# top.net
KiCad netlist of a schematic drawn in Altium Designer
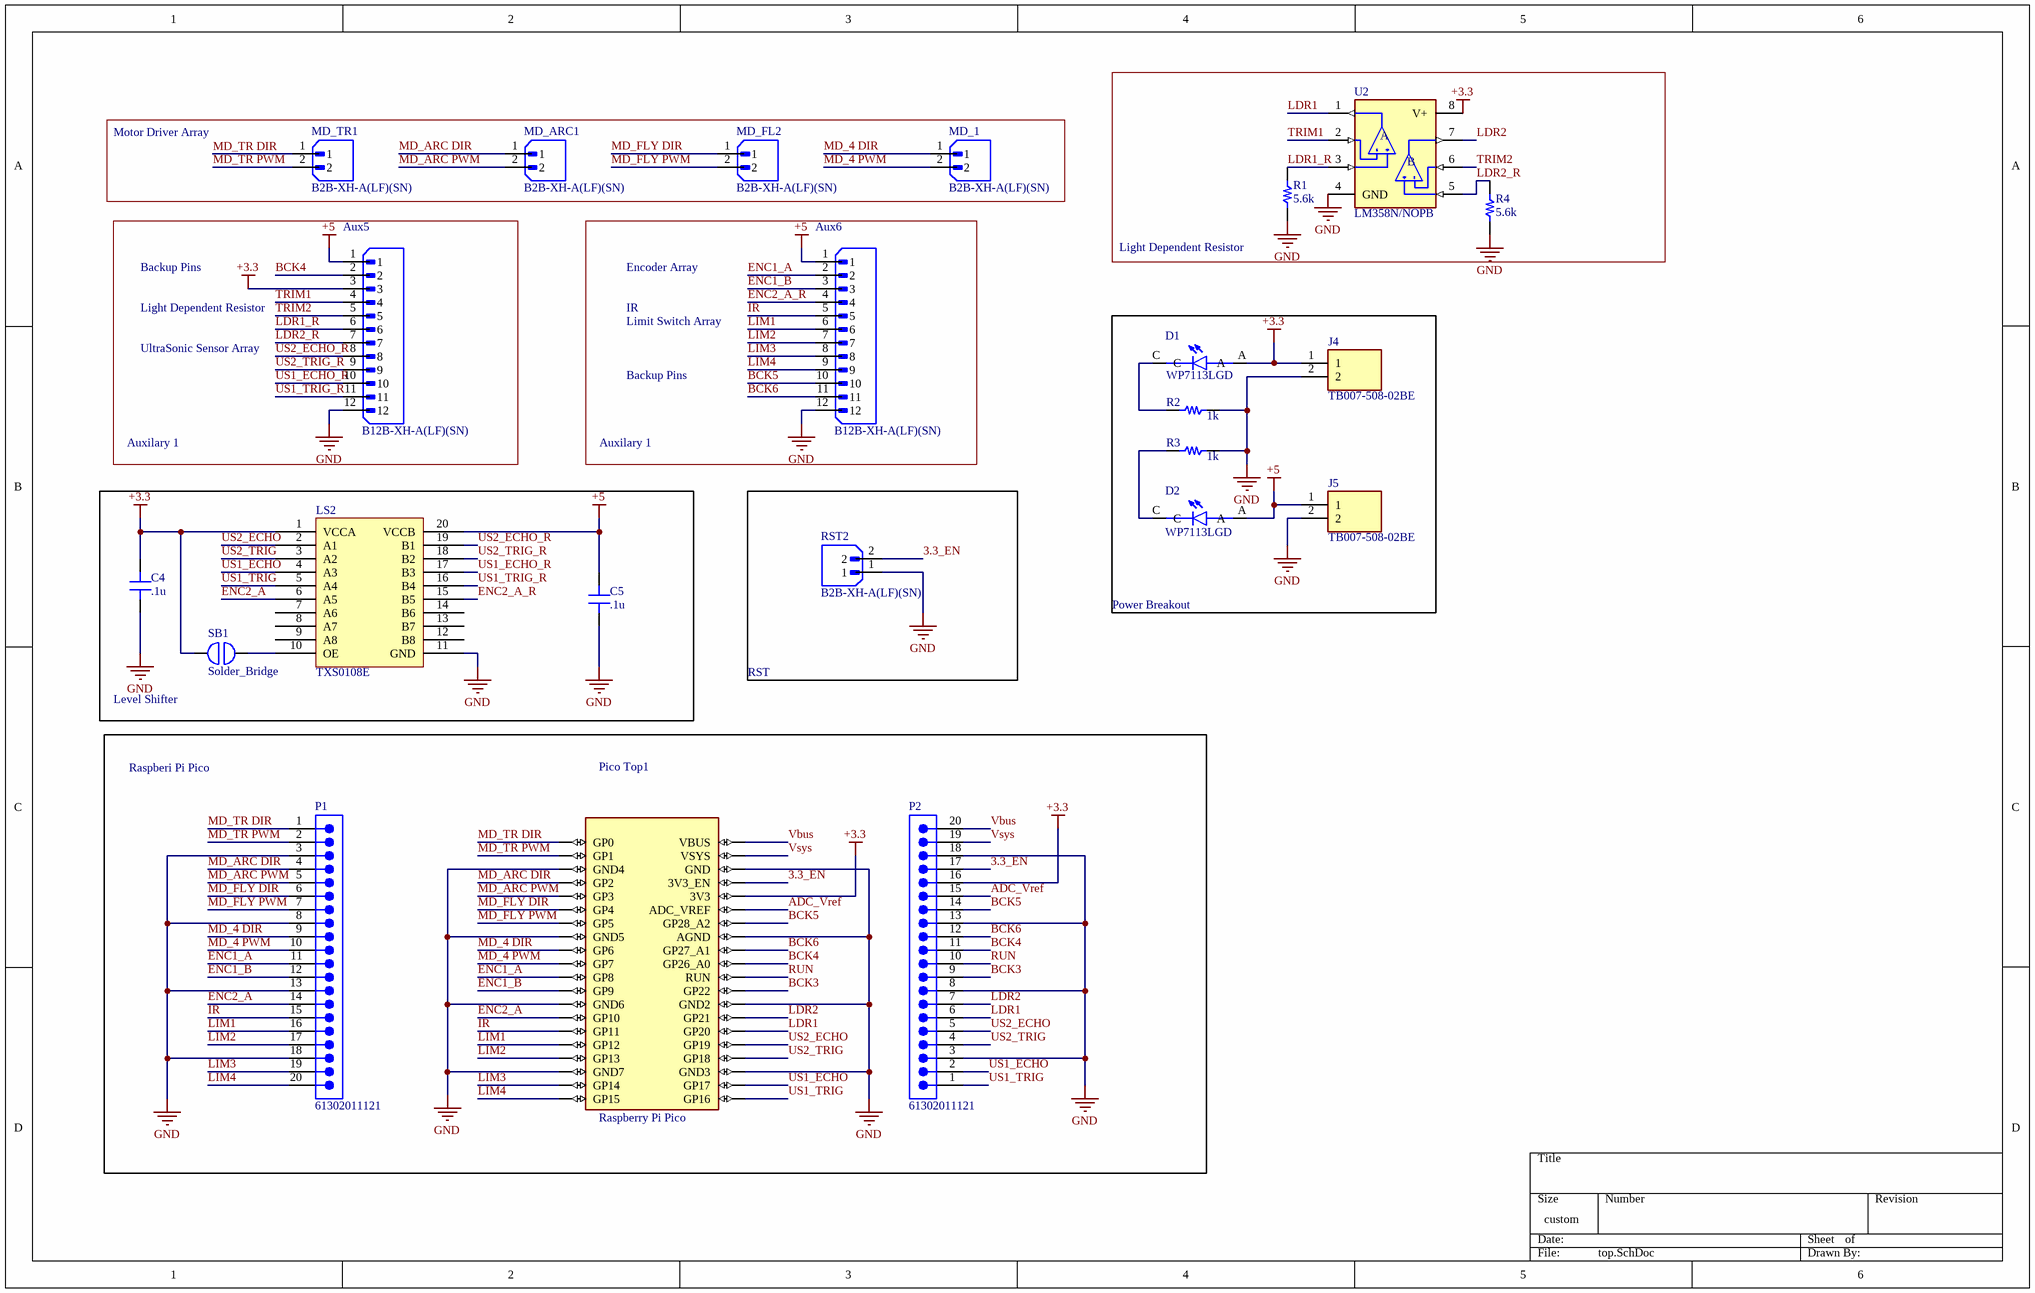
[diagram p0: top.SchDoc]

(export (version "E")
  (design (tool "Eeschema 10.0.6"))
  (components
    (comp (ref "Aux5")
      (value "B12B-XH-A(LF)(SN)")
      (footprint "JST_B12B-XH-A(LF)(SN)")
      (description "Connector Header Through Hole 12 position 0.098 (2.50mm)")
      (fields (field (name "MF") "JST Sales"))
      (libsource (lib "CSD Robocon Workspace") (part "B12B-XH-A(LF)(SN)"))
    )
    (comp (ref "Aux6")
      (value "B12B-XH-A(LF)(SN)")
      (footprint "JST_B12B-XH-A(LF)(SN)")
      (description "Connector Header Through Hole 12 position 0.098 (2.50mm)")
      (fields (field (name "MF") "JST Sales"))
      (libsource (lib "CSD Robocon Workspace") (part "B12B-XH-A(LF)(SN)"))
    )
    (comp (ref "C4")
      (value ".1u")
      (footprint "generic_cap")
      (description "Generic Ceramic Capacitor")
      (fields (field (name "MP") "RDER71H472K0K1H03B"))
      (libsource (lib "CSD Robocon Workspace") (part "generic_cap"))
    )
    (comp (ref "C5")
      (value ".1u")
      (footprint "generic_cap")
      (description "Generic Ceramic Capacitor")
      (fields (field (name "MP") "RDER71H472K0K1H03B"))
      (libsource (lib "CSD Robocon Workspace") (part "generic_cap"))
    )
    (comp (ref "D1")
      (value "WP7113LGD")
      (footprint "LED_WP7113LGD")
      (description "Green 568nm LED Indication - Discrete 1.9V Radial")
      (fields (field (name "MF") "Kingbright"))
      (libsource (lib "CSD Robocon Workspace") (part "WP7113LGD"))
    )
    (comp (ref "D2")
      (value "WP7113LGD")
      (footprint "LED_WP7113LGD")
      (description "Green 568nm LED Indication - Discrete 1.9V Radial")
      (fields (field (name "MF") "Kingbright"))
      (libsource (lib "CSD Robocon Workspace") (part "WP7113LGD"))
    )
    (comp (ref "J4")
      (value "TB007-508-02BE")
      (footprint "CUI_TB007-508-02BE")
      (description "Barrier Strip Terminal Block")
      (fields (field (name "MF") "{'manufacturer': u'CUI'}"))
      (libsource (lib "CSD Robocon Workspace") (part "TB007-508-02BE"))
    )
    (comp (ref "J5")
      (value "TB007-508-02BE")
      (footprint "CUI_TB007-508-02BE")
      (description "Barrier Strip Terminal Block")
      (fields (field (name "MF") "{'manufacturer': u'CUI'}"))
      (libsource (lib "CSD Robocon Workspace") (part "TB007-508-02BE"))
    )
    (comp (ref "LS2")
      (value "TXS0108E")
      (footprint "TXS0108E footprint")
      (description "8 Channel Logic Level Shifter module")
      (libsource (lib "CSD Robocon Workspace") (part "TXS0108E Symbol"))
    )
    (comp (ref "MD_1")
      (value "B2B-XH-A(LF)(SN)")
      (footprint "JST_B2B-XH-A(LF)(SN)")
      (description "Connector Header Through Hole 2 position 0.098 (2.50mm)")
      (fields (field (name "MF") "JST Sales America Inc."))
      (libsource (lib "") (part "B2B-XH-A(LF)(SN)_2"))
    )
    (comp (ref "MD_ARC1")
      (value "B2B-XH-A(LF)(SN)")
      (footprint "JST_B2B-XH-A(LF)(SN)")
      (description "Connector Header Through Hole 2 position 0.098 (2.50mm)")
      (fields (field (name "MF") "JST Sales America Inc."))
      (libsource (lib "") (part "B2B-XH-A(LF)(SN)_2"))
    )
    (comp (ref "MD_FL2")
      (value "B2B-XH-A(LF)(SN)")
      (footprint "JST_B2B-XH-A(LF)(SN)")
      (description "Connector Header Through Hole 2 position 0.098 (2.50mm)")
      (fields (field (name "MF") "JST Sales America Inc."))
      (libsource (lib "") (part "B2B-XH-A(LF)(SN)_2"))
    )
    (comp (ref "MD_TR1")
      (value "B2B-XH-A(LF)(SN)")
      (footprint "JST_B2B-XH-A(LF)(SN)")
      (description "Connector Header Through Hole 2 position 0.098 (2.50mm)")
      (fields (field (name "MF") "JST Sales America Inc."))
      (libsource (lib "CSD Robocon Workspace") (part "B2B-XH-A(LF)(SN)"))
    )
    (comp (ref "P1")
      (value "61302011121")
      (footprint "61302011121")
      (description "WR-PHD Pin Header, THT, Vertical, pitch 2.54mm, 1 Row, 20P")
      (fields (field (name "MANUFACTURER") "Wurth Elektronik"))
      (libsource (lib "CSD Robocon Workspace") (part "62002011121"))
    )
    (comp (ref "P2")
      (value "61302011121")
      (footprint "61302011121")
      (description "WR-PHD Pin Header, THT, Vertical, pitch 2.54mm, 1 Row, 20P")
      (fields (field (name "MANUFACTURER") "Wurth Elektronik"))
      (libsource (lib "CSD Robocon Workspace") (part "62002011121"))
    )
    (comp (ref "Pico Top1")
      (value "Raspberry Pi Pico")
      (footprint "RASPBERRY_PI_PICO")
      (description "Raspberry Pi Board, Arm Cortex-M0+")
      (fields (field (name "MF") "Raspberry Pi") (field (name "MP") "RASPBERRY PI PICO"))
      (libsource (lib "CSD Robocon Workspace") (part "Raspberry Pi Pico"))
    )
    (comp (ref "R1")
      (value "5.6k")
      (footprint "generic_res_footprint")
      (description "Generic through hole resistor")
      (libsource (lib "CSD Robocon Workspace") (part "generic_res"))
    )
    (comp (ref "R2")
      (value "1k")
      (footprint "generic_res_footprint")
      (description "Generic through hole resistor")
      (libsource (lib "CSD Robocon Workspace") (part "generic_res"))
    )
    (comp (ref "R3")
      (value "1k")
      (footprint "generic_res_footprint")
      (description "Generic through hole resistor")
      (libsource (lib "CSD Robocon Workspace") (part "generic_res"))
    )
    (comp (ref "R4")
      (value "5.6k")
      (footprint "generic_res_footprint")
      (description "Generic through hole resistor")
      (libsource (lib "CSD Robocon Workspace") (part "generic_res"))
    )
    (comp (ref "RST2")
      (value "B2B-XH-A(LF)(SN)")
      (footprint "JST_B2B-XH-A(LF)(SN)")
      (description "Connector Header Through Hole 2 position 0.098 (2.50mm)")
      (fields (field (name "MF") "JST Sales America Inc."))
      (libsource (lib "") (part "B2B-XH-A(LF)(SN)_1"))
    )
    (comp (ref "SB1")
      (value "Solder_Bridge")
      (footprint "Solder_Bridge-Footprint-1")
      (description "Solder bridge component")
      (libsource (lib "CSD Robocon Workspace") (part "SB_SYM"))
    )
    (comp (ref "U2")
      (value "LM358N/NOPB")
      (footprint "DIP794W45P254L959H508Q8")
      (description "General Purpose Amplifier 2 Circuit - 8-PDIP")
      (fields (field (name "MP") "LM358N") (field (name "MF") "ON Semiconductor"))
      (libsource (lib "CSD Robocon Workspace") (part "LM358N/NOPB"))
    )
  )
  (nets
    (net (code "1") (name "+3.3") (class "Default")
      (node (ref "Aux5") (pin "3") (pinfunction "3_3") (pintype "passive"))
      (node (ref "C4") (pin "2") (pinfunction "2_2") (pintype "passive"))
      (node (ref "D1") (pin "A") (pinfunction "A_A") (pintype "passive"))
      (node (ref "J4") (pin "1") (pinfunction "1_1") (pintype "passive"))
      (node (ref "LS2") (pin "1") (pinfunction "VCCA_1") (pintype "passive"))
      (node (ref "P2") (pin "16") (pinfunction "16_16") (pintype "passive"))
      (node (ref "Pico Top1") (pin "3V3") (pinfunction "3V3_3V3") (pintype "bidirectional"))
      (node (ref "SB1") (pin "1") (pinfunction "1_1") (pintype "passive"))
      (node (ref "U2") (pin "8") (pinfunction "V+_8") (pintype "power_in"))
    )
    (net (code "2") (name "+5") (class "Default")
      (node (ref "Aux5") (pin "1") (pinfunction "1_1") (pintype "passive"))
      (node (ref "Aux6") (pin "1") (pinfunction "1_1") (pintype "passive"))
      (node (ref "C5") (pin "2") (pinfunction "2_2") (pintype "passive"))
      (node (ref "D2") (pin "A") (pinfunction "A_A") (pintype "passive"))
      (node (ref "J5") (pin "1") (pinfunction "1_1") (pintype "passive"))
      (node (ref "LS2") (pin "20") (pinfunction "VCCB_20") (pintype "passive"))
    )
    (net (code "3") (name "/3.3_EN") (class "Default")
      (node (ref "P2") (pin "17") (pinfunction "17_17") (pintype "passive"))
      (node (ref "Pico Top1") (pin "3V3_EN") (pinfunction "3V3_EN_3V3_EN") (pintype "bidirectional"))
      (node (ref "RST2") (pin "2") (pinfunction "2_2") (pintype "passive"))
    )
    (net (code "4") (name "/ADC_Vref") (class "Default")
      (node (ref "P2") (pin "15") (pinfunction "15_15") (pintype "passive"))
      (node (ref "Pico Top1") (pin "ADC_VREF") (pinfunction "ADC_VREF_ADC_VREF") (pintype "bidirectional"))
    )
    (net (code "5") (name "/BCK3") (class "Default")
      (node (ref "P2") (pin "9") (pinfunction "9_9") (pintype "passive"))
      (node (ref "Pico Top1") (pin "GP22") (pinfunction "GP22_GP22") (pintype "bidirectional"))
    )
    (net (code "6") (name "/BCK4") (class "Default")
      (node (ref "Aux5") (pin "2") (pinfunction "2_2") (pintype "passive"))
      (node (ref "P2") (pin "11") (pinfunction "11_11") (pintype "passive"))
      (node (ref "Pico Top1") (pin "GP26_A0") (pinfunction "GP26_A0_GP26_A0") (pintype "bidirectional"))
    )
    (net (code "7") (name "/BCK5") (class "Default")
      (node (ref "Aux6") (pin "10") (pinfunction "10_10") (pintype "passive"))
      (node (ref "P2") (pin "14") (pinfunction "14_14") (pintype "passive"))
      (node (ref "Pico Top1") (pin "GP28_A2") (pinfunction "GP28_A2_GP28_A2") (pintype "bidirectional"))
    )
    (net (code "8") (name "/BCK6") (class "Default")
      (node (ref "Aux6") (pin "11") (pinfunction "11_11") (pintype "passive"))
      (node (ref "P2") (pin "12") (pinfunction "12_12") (pintype "passive"))
      (node (ref "Pico Top1") (pin "GP27_A1") (pinfunction "GP27_A1_GP27_A1") (pintype "bidirectional"))
    )
    (net (code "9") (name "/ENC1_A") (class "Default")
      (node (ref "Aux6") (pin "2") (pinfunction "2_2") (pintype "passive"))
      (node (ref "P1") (pin "11") (pinfunction "11_11") (pintype "passive"))
      (node (ref "Pico Top1") (pin "GP8") (pinfunction "GP8_GP8") (pintype "bidirectional"))
    )
    (net (code "10") (name "/ENC1_B") (class "Default")
      (node (ref "Aux6") (pin "3") (pinfunction "3_3") (pintype "passive"))
      (node (ref "P1") (pin "12") (pinfunction "12_12") (pintype "passive"))
      (node (ref "Pico Top1") (pin "GP9") (pinfunction "GP9_GP9") (pintype "bidirectional"))
    )
    (net (code "11") (name "/ENC2_A") (class "Default")
      (node (ref "LS2") (pin "6") (pinfunction "A5_6") (pintype "passive"))
      (node (ref "P1") (pin "14") (pinfunction "14_14") (pintype "passive"))
      (node (ref "Pico Top1") (pin "GP10") (pinfunction "GP10_GP10") (pintype "bidirectional"))
    )
    (net (code "12") (name "/ENC2_A_R") (class "Default")
      (node (ref "Aux6") (pin "4") (pinfunction "4_4") (pintype "passive"))
      (node (ref "LS2") (pin "15") (pinfunction "B5_15") (pintype "passive"))
    )
    (net (code "13") (name "/IR") (class "Default")
      (node (ref "Aux6") (pin "5") (pinfunction "5_5") (pintype "passive"))
      (node (ref "P1") (pin "15") (pinfunction "15_15") (pintype "passive"))
      (node (ref "Pico Top1") (pin "GP11") (pinfunction "GP11_GP11") (pintype "bidirectional"))
    )
    (net (code "14") (name "/LDR1") (class "Default")
      (node (ref "P2") (pin "6") (pinfunction "6_6") (pintype "passive"))
      (node (ref "Pico Top1") (pin "GP20") (pinfunction "GP20_GP20") (pintype "bidirectional"))
      (node (ref "U2") (pin "1") (pinfunction "OUTA_1") (pintype "output"))
    )
    (net (code "15") (name "/LDR1_R") (class "Default")
      (node (ref "Aux5") (pin "6") (pinfunction "6_6") (pintype "passive"))
      (node (ref "R1") (pin "2") (pinfunction "2_2") (pintype "passive"))
      (node (ref "U2") (pin "3") (pinfunction "+INA_3") (pintype "input"))
    )
    (net (code "16") (name "/LDR2") (class "Default")
      (node (ref "P2") (pin "7") (pinfunction "7_7") (pintype "passive"))
      (node (ref "Pico Top1") (pin "GP21") (pinfunction "GP21_GP21") (pintype "bidirectional"))
      (node (ref "U2") (pin "7") (pinfunction "OUTB_7") (pintype "output"))
    )
    (net (code "17") (name "/LDR2_R") (class "Default")
      (node (ref "Aux5") (pin "7") (pinfunction "7_7") (pintype "passive"))
      (node (ref "R4") (pin "2") (pinfunction "2_2") (pintype "passive"))
      (node (ref "U2") (pin "5") (pinfunction "+INB_5") (pintype "input"))
    )
    (net (code "18") (name "/LIM1") (class "Default")
      (node (ref "Aux6") (pin "6") (pinfunction "6_6") (pintype "passive"))
      (node (ref "P1") (pin "16") (pinfunction "16_16") (pintype "passive"))
      (node (ref "Pico Top1") (pin "GP12") (pinfunction "GP12_GP12") (pintype "bidirectional"))
    )
    (net (code "19") (name "/LIM2") (class "Default")
      (node (ref "Aux6") (pin "7") (pinfunction "7_7") (pintype "passive"))
      (node (ref "P1") (pin "17") (pinfunction "17_17") (pintype "passive"))
      (node (ref "Pico Top1") (pin "GP13") (pinfunction "GP13_GP13") (pintype "bidirectional"))
    )
    (net (code "20") (name "/LIM3") (class "Default")
      (node (ref "Aux6") (pin "8") (pinfunction "8_8") (pintype "passive"))
      (node (ref "P1") (pin "19") (pinfunction "19_19") (pintype "passive"))
      (node (ref "Pico Top1") (pin "GP14") (pinfunction "GP14_GP14") (pintype "bidirectional"))
    )
    (net (code "21") (name "/LIM4") (class "Default")
      (node (ref "Aux6") (pin "9") (pinfunction "9_9") (pintype "passive"))
      (node (ref "P1") (pin "20") (pinfunction "20_20") (pintype "passive"))
      (node (ref "Pico Top1") (pin "GP15") (pinfunction "GP15_GP15") (pintype "bidirectional"))
    )
    (net (code "22") (name "/MD_4 DIR") (class "Default")
      (node (ref "MD_1") (pin "1") (pinfunction "1_1") (pintype "passive"))
      (node (ref "P1") (pin "9") (pinfunction "9_9") (pintype "passive"))
      (node (ref "Pico Top1") (pin "GP6") (pinfunction "GP6_GP6") (pintype "bidirectional"))
    )
    (net (code "23") (name "/MD_4 PWM") (class "Default")
      (node (ref "MD_1") (pin "2") (pinfunction "2_2") (pintype "passive"))
      (node (ref "P1") (pin "10") (pinfunction "10_10") (pintype "passive"))
      (node (ref "Pico Top1") (pin "GP7") (pinfunction "GP7_GP7") (pintype "bidirectional"))
    )
    (net (code "24") (name "/MD_ARC DIR") (class "Default")
      (node (ref "MD_ARC1") (pin "1") (pinfunction "1_1") (pintype "passive"))
      (node (ref "P1") (pin "4") (pinfunction "4_4") (pintype "passive"))
      (node (ref "Pico Top1") (pin "GP2") (pinfunction "GP2_GP2") (pintype "bidirectional"))
    )
    (net (code "25") (name "/MD_ARC PWM") (class "Default")
      (node (ref "MD_ARC1") (pin "2") (pinfunction "2_2") (pintype "passive"))
      (node (ref "P1") (pin "5") (pinfunction "5_5") (pintype "passive"))
      (node (ref "Pico Top1") (pin "GP3") (pinfunction "GP3_GP3") (pintype "bidirectional"))
    )
    (net (code "26") (name "/MD_FLY DIR") (class "Default")
      (node (ref "MD_FL2") (pin "1") (pinfunction "1_1") (pintype "passive"))
      (node (ref "P1") (pin "6") (pinfunction "6_6") (pintype "passive"))
      (node (ref "Pico Top1") (pin "GP4") (pinfunction "GP4_GP4") (pintype "bidirectional"))
    )
    (net (code "27") (name "/MD_FLY PWM") (class "Default")
      (node (ref "MD_FL2") (pin "2") (pinfunction "2_2") (pintype "passive"))
      (node (ref "P1") (pin "7") (pinfunction "7_7") (pintype "passive"))
      (node (ref "Pico Top1") (pin "GP5") (pinfunction "GP5_GP5") (pintype "bidirectional"))
    )
    (net (code "28") (name "/MD_TR DIR") (class "Default")
      (node (ref "MD_TR1") (pin "1") (pinfunction "1_1") (pintype "passive"))
      (node (ref "P1") (pin "1") (pinfunction "1_1") (pintype "passive"))
      (node (ref "Pico Top1") (pin "GP0") (pinfunction "GP0_GP0") (pintype "bidirectional"))
    )
    (net (code "29") (name "/MD_TR PWM") (class "Default")
      (node (ref "MD_TR1") (pin "2") (pinfunction "2_2") (pintype "passive"))
      (node (ref "P1") (pin "2") (pinfunction "2_2") (pintype "passive"))
      (node (ref "Pico Top1") (pin "GP1") (pinfunction "GP1_GP1") (pintype "bidirectional"))
    )
    (net (code "30") (name "/RUN") (class "Default")
      (node (ref "P2") (pin "10") (pinfunction "10_10") (pintype "passive"))
      (node (ref "Pico Top1") (pin "RUN") (pinfunction "RUN_RUN") (pintype "bidirectional"))
    )
    (net (code "31") (name "/TRIM1") (class "Default")
      (node (ref "Aux5") (pin "4") (pinfunction "4_4") (pintype "passive"))
      (node (ref "U2") (pin "2") (pinfunction "-INA_2") (pintype "input"))
    )
    (net (code "32") (name "/TRIM2") (class "Default")
      (node (ref "Aux5") (pin "5") (pinfunction "5_5") (pintype "passive"))
      (node (ref "U2") (pin "6") (pinfunction "-INB_6") (pintype "input"))
    )
    (net (code "33") (name "/US1_ECHO") (class "Default")
      (node (ref "LS2") (pin "4") (pinfunction "A3_4") (pintype "passive"))
      (node (ref "P2") (pin "2") (pinfunction "2_2") (pintype "passive"))
      (node (ref "Pico Top1") (pin "GP17") (pinfunction "GP17_GP17") (pintype "bidirectional"))
    )
    (net (code "34") (name "/US1_ECHO_R") (class "Default")
      (node (ref "Aux5") (pin "10") (pinfunction "10_10") (pintype "passive"))
      (node (ref "LS2") (pin "17") (pinfunction "B3_17") (pintype "passive"))
    )
    (net (code "35") (name "/US1_TRIG") (class "Default")
      (node (ref "LS2") (pin "5") (pinfunction "A4_5") (pintype "passive"))
      (node (ref "P2") (pin "1") (pinfunction "1_1") (pintype "passive"))
      (node (ref "Pico Top1") (pin "GP16") (pinfunction "GP16_GP16") (pintype "bidirectional"))
    )
    (net (code "36") (name "/US1_TRIG_R") (class "Default")
      (node (ref "Aux5") (pin "11") (pinfunction "11_11") (pintype "passive"))
      (node (ref "LS2") (pin "16") (pinfunction "B4_16") (pintype "passive"))
    )
    (net (code "37") (name "/US2_ECHO") (class "Default")
      (node (ref "LS2") (pin "2") (pinfunction "A1_2") (pintype "passive"))
      (node (ref "P2") (pin "5") (pinfunction "5_5") (pintype "passive"))
      (node (ref "Pico Top1") (pin "GP19") (pinfunction "GP19_GP19") (pintype "bidirectional"))
    )
    (net (code "38") (name "/US2_ECHO_R") (class "Default")
      (node (ref "Aux5") (pin "8") (pinfunction "8_8") (pintype "passive"))
      (node (ref "LS2") (pin "19") (pinfunction "B1_19") (pintype "passive"))
    )
    (net (code "39") (name "/US2_TRIG") (class "Default")
      (node (ref "LS2") (pin "3") (pinfunction "A2_3") (pintype "passive"))
      (node (ref "P2") (pin "4") (pinfunction "4_4") (pintype "passive"))
      (node (ref "Pico Top1") (pin "GP18") (pinfunction "GP18_GP18") (pintype "bidirectional"))
    )
    (net (code "40") (name "/US2_TRIG_R") (class "Default")
      (node (ref "Aux5") (pin "9") (pinfunction "9_9") (pintype "passive"))
      (node (ref "LS2") (pin "18") (pinfunction "B2_18") (pintype "passive"))
    )
    (net (code "41") (name "/Vbus") (class "Default")
      (node (ref "P2") (pin "20") (pinfunction "20_20") (pintype "passive"))
      (node (ref "Pico Top1") (pin "VBUS") (pinfunction "VBUS_VBUS") (pintype "bidirectional"))
    )
    (net (code "42") (name "/Vsys") (class "Default")
      (node (ref "P2") (pin "19") (pinfunction "19_19") (pintype "passive"))
      (node (ref "Pico Top1") (pin "VSYS") (pinfunction "VSYS_VSYS") (pintype "bidirectional"))
    )
    (net (code "43") (name "GND") (class "Default")
      (node (ref "Aux5") (pin "12") (pinfunction "12_12") (pintype "passive"))
      (node (ref "Aux6") (pin "12") (pinfunction "12_12") (pintype "passive"))
      (node (ref "C4") (pin "1") (pinfunction "1_1") (pintype "passive"))
      (node (ref "C5") (pin "1") (pinfunction "1_1") (pintype "passive"))
      (node (ref "J4") (pin "2") (pinfunction "2_2") (pintype "passive"))
      (node (ref "J5") (pin "2") (pinfunction "2_2") (pintype "passive"))
      (node (ref "LS2") (pin "11") (pinfunction "GND_11") (pintype "passive"))
      (node (ref "P1") (pin "13") (pinfunction "13_13") (pintype "passive"))
      (node (ref "P1") (pin "18") (pinfunction "18_18") (pintype "passive"))
      (node (ref "P1") (pin "3") (pinfunction "3_3") (pintype "passive"))
      (node (ref "P1") (pin "8") (pinfunction "8_8") (pintype "passive"))
      (node (ref "P2") (pin "13") (pinfunction "13_13") (pintype "passive"))
      (node (ref "P2") (pin "18") (pinfunction "18_18") (pintype "passive"))
      (node (ref "P2") (pin "3") (pinfunction "3_3") (pintype "passive"))
      (node (ref "P2") (pin "8") (pinfunction "8_8") (pintype "passive"))
      (node (ref "Pico Top1") (pin "AGND") (pinfunction "AGND_AGND") (pintype "bidirectional"))
      (node (ref "Pico Top1") (pin "GND") (pinfunction "GND_GND") (pintype "bidirectional"))
      (node (ref "Pico Top1") (pin "GND2") (pinfunction "GND2_GND2") (pintype "bidirectional"))
      (node (ref "Pico Top1") (pin "GND3") (pinfunction "GND3_GND3") (pintype "bidirectional"))
      (node (ref "Pico Top1") (pin "GND4") (pinfunction "GND4_GND4") (pintype "bidirectional"))
      (node (ref "Pico Top1") (pin "GND5") (pinfunction "GND5_GND5") (pintype "bidirectional"))
      (node (ref "Pico Top1") (pin "GND6") (pinfunction "GND6_GND6") (pintype "bidirectional"))
      (node (ref "Pico Top1") (pin "GND7") (pinfunction "GND7_GND7") (pintype "bidirectional"))
      (node (ref "R1") (pin "1") (pinfunction "1_1") (pintype "passive"))
      (node (ref "R2") (pin "2") (pinfunction "2_2") (pintype "passive"))
      (node (ref "R3") (pin "2") (pinfunction "2_2") (pintype "passive"))
      (node (ref "R4") (pin "1") (pinfunction "1_1") (pintype "passive"))
      (node (ref "RST2") (pin "1") (pinfunction "1_1") (pintype "passive"))
      (node (ref "U2") (pin "4") (pinfunction "GND_4") (pintype "power_in"))
    )
    (net (code "44") (name "Net-(D1-PadC)") (class "Default")
      (node (ref "D1") (pin "C") (pinfunction "C_C") (pintype "passive"))
      (node (ref "R2") (pin "1") (pinfunction "1_1") (pintype "passive"))
    )
    (net (code "45") (name "Net-(D2-PadC)") (class "Default")
      (node (ref "D2") (pin "C") (pinfunction "C_C") (pintype "passive"))
      (node (ref "R3") (pin "1") (pinfunction "1_1") (pintype "passive"))
    )
    (net (code "46") (name "Net-(LS2-OE)") (class "Default")
      (node (ref "LS2") (pin "10") (pinfunction "OE_10") (pintype "passive"))
      (node (ref "SB1") (pin "2") (pinfunction "2_2") (pintype "passive"))
    )
    (net (code "47") (name "unconnected-(LS2-A6-Pad7)") (class "Default")
      (node (ref "LS2") (pin "7") (pinfunction "A6_7") (pintype "passive"))
    )
    (net (code "48") (name "unconnected-(LS2-A7-Pad8)") (class "Default")
      (node (ref "LS2") (pin "8") (pinfunction "A7_8") (pintype "passive"))
    )
    (net (code "49") (name "unconnected-(LS2-A8-Pad9)") (class "Default")
      (node (ref "LS2") (pin "9") (pinfunction "A8_9") (pintype "passive"))
    )
    (net (code "50") (name "unconnected-(LS2-B6-Pad14)") (class "Default")
      (node (ref "LS2") (pin "14") (pinfunction "B6_14") (pintype "passive"))
    )
    (net (code "51") (name "unconnected-(LS2-B7-Pad13)") (class "Default")
      (node (ref "LS2") (pin "13") (pinfunction "B7_13") (pintype "passive"))
    )
    (net (code "52") (name "unconnected-(LS2-B8-Pad12)") (class "Default")
      (node (ref "LS2") (pin "12") (pinfunction "B8_12") (pintype "passive"))
    )
  )
)
